# sensor.net
KiCad netlist of a schematic drawn in Altium Designer
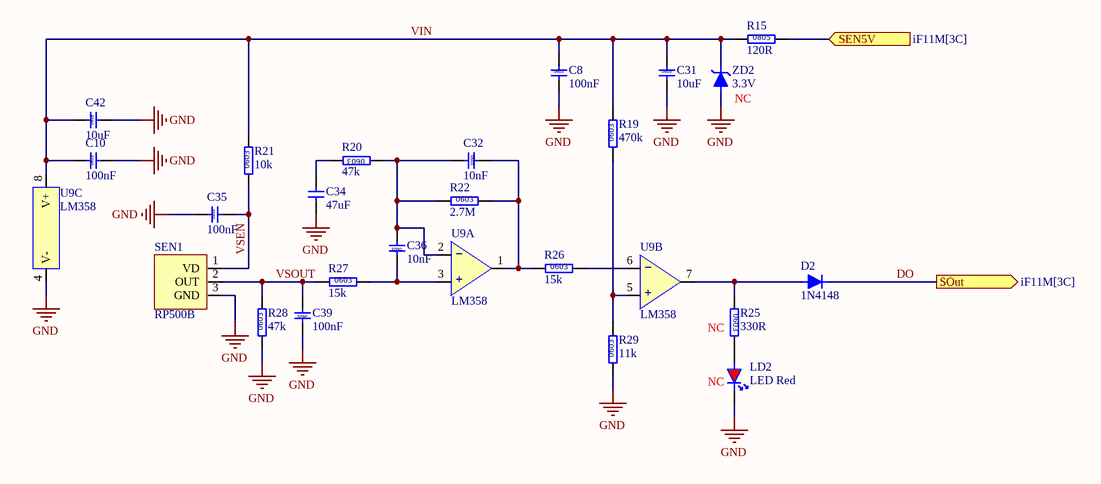
[diagram p0: sensor.SchDoc]

(export (version "E")
  (design (tool "Eeschema 10.0.6"))
  (components
    (comp (ref "C8")
      (value "100nF")
      (footprint "C0603")
      (description "10% 50V")
      (fields (field (name "PART NO") "W-T-CA-X703N100K50VNT") (field (name "MANUFACTURER") "FENGHUA"))
      (libsource (lib "Rescap") (part "C 0603 100nF 50V"))
    )
    (comp (ref "C10")
      (value "100nF")
      (footprint "C0603")
      (description "10% 50V")
      (fields (field (name "PART NO") "W-T-CA-X703N100K50VNT") (field (name "MANUFACTURER") "FENGHUA"))
      (libsource (lib "Rescap") (part "C 0603 100nF 50V"))
    )
    (comp (ref "C31")
      (value "10uF")
      (footprint "C0805")
      (description "10% 25V")
      (fields (field (name "PART NO") "WP0005368"))
      (libsource (lib "Rescap") (part "C 0805 10uF 25V"))
    )
    (comp (ref "C32")
      (value "10nF")
      (footprint "C0603")
      (description "10% 50V")
      (fields (field (name "PART NO") "W-T-CA-X703N10K50VNT"))
      (libsource (lib "Rescap") (part "C 0603 10nF 50V"))
    )
    (comp (ref "C34")
      (value "47uF")
      (footprint "C0603")
      (description "SMD resistor  Package")
      (libsource (lib "Capacitors") (part "Capacitor"))
    )
    (comp (ref "C35")
      (value "100nF")
      (footprint "C0805")
      (description "10% 50V")
      (fields (field (name "PART NO") "W-T-CA-X705N100K50VNT"))
      (libsource (lib "Rescap") (part "C 0805 100nF 50V"))
    )
    (comp (ref "C36")
      (value "10nF")
      (footprint "C0603")
      (description "10% 50V")
      (fields (field (name "PART NO") "W-T-CA-X703N10K50VNT"))
      (libsource (lib "Rescap") (part "C 0603 10nF 50V"))
    )
    (comp (ref "C39")
      (value "100nF")
      (footprint "C0805")
      (description "10% 50V")
      (fields (field (name "PART NO") "W-T-CA-X705N100K50VNT"))
      (libsource (lib "Rescap") (part "C 0805 100nF 50V"))
    )
    (comp (ref "C42")
      (value "10uF")
      (footprint "C0805")
      (description "10% 25V")
      (fields (field (name "PART NO") "WP0005368"))
      (libsource (lib "Rescap") (part "C 0805 10uF 25V"))
    )
    (comp (ref "D2")
      (value "1N4148")
      (footprint "SOD-323")
      (fields (field (name "PART NO") "W-T-DE-1N4148-SOD123"))
      (libsource (lib "Rectifier") (part "IN4148"))
    )
    (comp (ref "LD2")
      (value "LED Red")
      (footprint "LED-0603-RED")
      (libsource (lib "Optoelectronics") (part "LED Red"))
    )
    (comp (ref "R15")
      (value "120R")
      (footprint "R0805-LD")
      (description "5%")
      (fields (field (name "PART NO") "W-T-RE-RS05K121JT"))
      (libsource (lib "Rescap") (part "R 0805 120R"))
    )
    (comp (ref "R19")
      (value "470k")
      (footprint "R0603-LD")
      (description "5%")
      (fields (field (name "PART NO") "W-T-RE-RS03K153JT") (field (name "MANUFACTURER") "改善传感器，2023/01/08新增"))
      (libsource (lib "Rescap") (part "R 0603 15k"))
    )
    (comp (ref "R20")
      (value "47k")
      (footprint "R0603-LD")
      (description "5%")
      (fields (field (name "PART NO") "W-T-RE-RS03K473JT"))
      (libsource (lib "Rescap") (part "R 0603 47k"))
    )
    (comp (ref "R21")
      (value "10k")
      (footprint "R0603-LD")
      (description "5%")
      (fields (field (name "PART NO") "W-T-RE-RS03K103JT") (field (name "MANUFACTURER") "热敏D541V11增加1颗用量"))
      (libsource (lib "Rescap") (part "R 0603 10k"))
    )
    (comp (ref "R22")
      (value "2.7M")
      (footprint "R0603-LD")
      (description "5%")
      (fields (field (name "PART NO") "W-T-RE-RS03K473JT"))
      (libsource (lib "Rescap") (part "R 0603 47k"))
    )
    (comp (ref "R25")
      (value "330R")
      (footprint "R0603-LD")
      (description "5%")
      (fields (field (name "PART NO") "W-T-RE-RS03K331JT"))
      (libsource (lib "Rescap") (part "R 0603 330R"))
    )
    (comp (ref "R26")
      (value "15k")
      (footprint "R0603-LD")
      (description "5%")
      (fields (field (name "PART NO") "W-T-RE-RS03K153JT") (field (name "MANUFACTURER") "改善传感器，2023/01/08新增"))
      (libsource (lib "Rescap") (part "R 0603 15k"))
    )
    (comp (ref "R27")
      (value "15k")
      (footprint "R0603-LD")
      (description "5%")
      (fields (field (name "PART NO") "W-T-RE-RS03K153JT") (field (name "MANUFACTURER") "改善传感器，2023/01/08新增"))
      (libsource (lib "Rescap") (part "R 0603 15k"))
    )
    (comp (ref "R28")
      (value "47k")
      (footprint "R0603-LD")
      (description "5%")
      (fields (field (name "PART NO") "W-T-RE-RS03K473JT"))
      (libsource (lib "Rescap") (part "R 0603 47k"))
    )
    (comp (ref "R29")
      (value "11k")
      (footprint "R0603-LD")
      (description "5%")
      (fields (field (name "PART NO") "W-T-RE-RS03K103JT") (field (name "MANUFACTURER") "热敏D541V11增加1颗用量"))
      (libsource (lib "Rescap") (part "R 0603 10k"))
    )
    (comp (ref "SEN1") (value "RP500B") (footprint "TO-5-Lbent") (libsource (lib "Sensor") (part "RP500B")))
    (comp (ref "U9")
      (value "LM358")
      (footprint "LM358-SOIC8")
      (description "DUAL OPAMP")
      (libsource (lib "mylib2") (part "LM358"))
    )
    (comp (ref "ZD2")
      (value "3.3V")
      (footprint "SOD-323")
      (description "Zener Diode 300mW")
      (libsource (lib "Rectifier") (part "Zener Diode"))
    )
  )
  (nets
    (net (code "1") (name "/DO") (class "Default")
      (node (ref "D2") (pin "2") (pinfunction "K_2") (pintype "passive"))
    )
    (net (code "2") (name "/SEN5V") (class "Default")
      (node (ref "R15") (pin "2") (pinfunction "2_2") (pintype "passive"))
    )
    (net (code "3") (name "/VIN") (class "Default")
      (node (ref "C10") (pin "1") (pinfunction "1_1") (pintype "passive"))
      (node (ref "C31") (pin "1") (pinfunction "1_1") (pintype "passive"))
      (node (ref "C42") (pin "1") (pinfunction "1_1") (pintype "passive"))
      (node (ref "C8") (pin "1") (pinfunction "1_1") (pintype "passive"))
      (node (ref "R15") (pin "1") (pinfunction "1_1") (pintype "passive"))
      (node (ref "R19") (pin "2") (pinfunction "2_2") (pintype "passive"))
      (node (ref "R21") (pin "2") (pinfunction "2_2") (pintype "passive"))
      (node (ref "U9") (pin "8") (pinfunction "V+_8") (pintype "passive"))
      (node (ref "ZD2") (pin "2") (pinfunction "K_2") (pintype "passive"))
    )
    (net (code "4") (name "/VSEN") (class "Default")
      (node (ref "C35") (pin "2") (pinfunction "2_2") (pintype "passive"))
      (node (ref "R21") (pin "1") (pinfunction "1_1") (pintype "passive"))
      (node (ref "SEN1") (pin "1") (pinfunction "VD_1") (pintype "passive"))
    )
    (net (code "5") (name "/VSOUT") (class "Default")
      (node (ref "C39") (pin "2") (pinfunction "2_2") (pintype "passive"))
      (node (ref "R27") (pin "1") (pinfunction "1_1") (pintype "passive"))
      (node (ref "R28") (pin "2") (pinfunction "2_2") (pintype "passive"))
      (node (ref "SEN1") (pin "2") (pinfunction "OUT_2") (pintype "passive"))
    )
    (net (code "6") (name "GND") (class "Default")
      (node (ref "C10") (pin "2") (pinfunction "2_2") (pintype "passive"))
      (node (ref "C31") (pin "2") (pinfunction "2_2") (pintype "passive"))
      (node (ref "C34") (pin "2") (pinfunction "2_2") (pintype "passive"))
      (node (ref "C35") (pin "1") (pinfunction "1_1") (pintype "passive"))
      (node (ref "C39") (pin "1") (pinfunction "1_1") (pintype "passive"))
      (node (ref "C42") (pin "2") (pinfunction "2_2") (pintype "passive"))
      (node (ref "C8") (pin "2") (pinfunction "2_2") (pintype "passive"))
      (node (ref "LD2") (pin "2") (pinfunction "K_2") (pintype "passive"))
      (node (ref "R28") (pin "1") (pinfunction "1_1") (pintype "passive"))
      (node (ref "R29") (pin "1") (pinfunction "1_1") (pintype "passive"))
      (node (ref "SEN1") (pin "3") (pinfunction "GND_3") (pintype "passive"))
      (node (ref "U9") (pin "4") (pinfunction "V-_4") (pintype "passive"))
      (node (ref "ZD2") (pin "1") (pinfunction "A_1") (pintype "passive"))
    )
    (net (code "7") (name "Net-(C34-Pad1)") (class "Default")
      (node (ref "C34") (pin "1") (pinfunction "1_1") (pintype "passive"))
      (node (ref "R20") (pin "2") (pinfunction "2_2") (pintype "passive"))
    )
    (net (code "8") (name "Net-(D2-A)") (class "Default")
      (node (ref "D2") (pin "1") (pinfunction "A_1") (pintype "passive"))
      (node (ref "R25") (pin "1") (pinfunction "1_1") (pintype "passive"))
      (node (ref "U9") (pin "7") (pinfunction "O2_7") (pintype "passive"))
    )
    (net (code "9") (name "Net-(LD2-A)") (class "Default")
      (node (ref "LD2") (pin "1") (pinfunction "A_1") (pintype "passive"))
      (node (ref "R25") (pin "2") (pinfunction "2_2") (pintype "passive"))
    )
    (net (code "10") (name "Net-(U9A-+)") (class "Default")
      (node (ref "C36") (pin "1") (pinfunction "1_1") (pintype "passive"))
      (node (ref "R27") (pin "2") (pinfunction "2_2") (pintype "passive"))
      (node (ref "U9") (pin "3") (pinfunction "+_3") (pintype "passive"))
    )
    (net (code "11") (name "Net-(U9A--)") (class "Default")
      (node (ref "C32") (pin "2") (pinfunction "2_2") (pintype "passive"))
      (node (ref "C36") (pin "2") (pinfunction "2_2") (pintype "passive"))
      (node (ref "R20") (pin "1") (pinfunction "1_1") (pintype "passive"))
      (node (ref "R22") (pin "1") (pinfunction "1_1") (pintype "passive"))
      (node (ref "U9") (pin "2") (pinfunction "-_2") (pintype "passive"))
    )
    (net (code "12") (name "Net-(U9A-O1)") (class "Default")
      (node (ref "C32") (pin "1") (pinfunction "1_1") (pintype "passive"))
      (node (ref "R22") (pin "2") (pinfunction "2_2") (pintype "passive"))
      (node (ref "R26") (pin "1") (pinfunction "1_1") (pintype "passive"))
      (node (ref "U9") (pin "1") (pinfunction "O1_1") (pintype "passive"))
    )
    (net (code "13") (name "Net-(U9B-+)") (class "Default")
      (node (ref "R19") (pin "1") (pinfunction "1_1") (pintype "passive"))
      (node (ref "R29") (pin "2") (pinfunction "2_2") (pintype "passive"))
      (node (ref "U9") (pin "5") (pinfunction "+_5") (pintype "passive"))
    )
    (net (code "14") (name "Net-(U9B--)") (class "Default")
      (node (ref "R26") (pin "2") (pinfunction "2_2") (pintype "passive"))
      (node (ref "U9") (pin "6") (pinfunction "-_6") (pintype "passive"))
    )
  )
)
